# CAN_Module.net
KiCad netlist of a schematic drawn in EAGLE
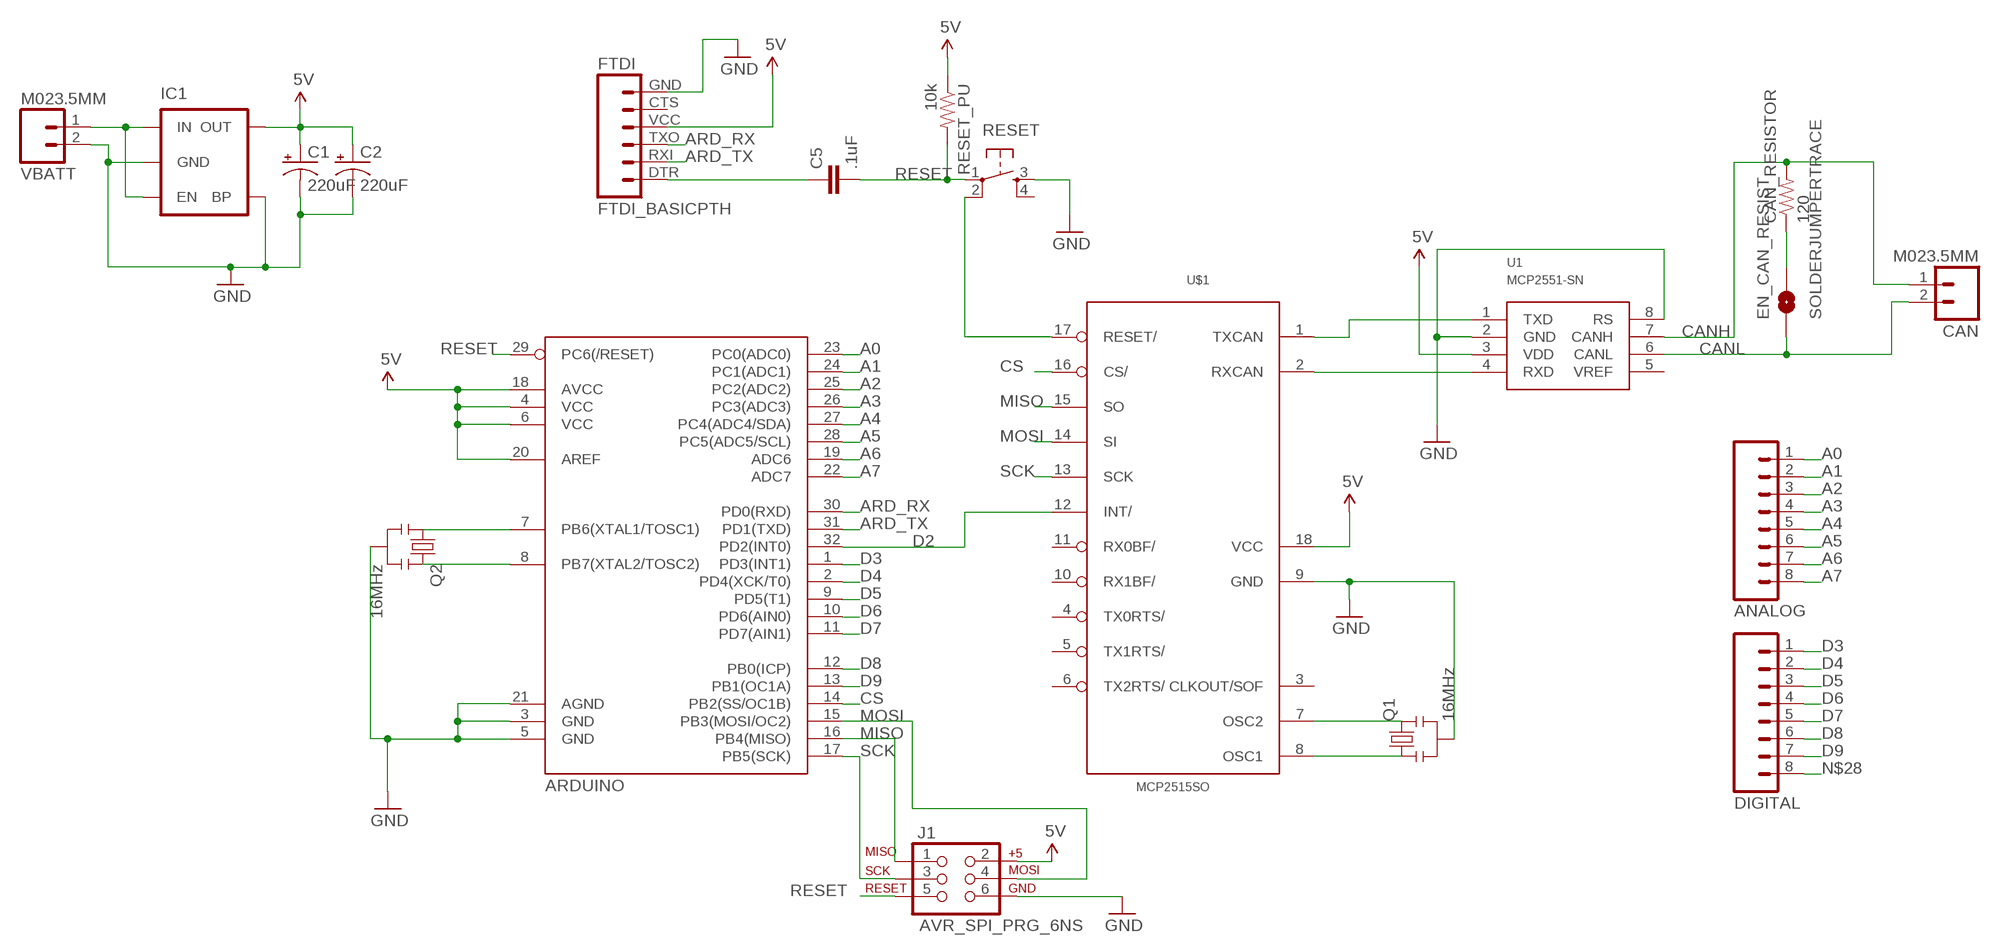
[diagram p0: schematic, sheet 1]

(export (version "E")
  (design (tool "Eeschema 10.0.6"))
  (components
    (comp (ref "ANALOG")
      (value "M08LOCK")
      (footprint "eagle-import:1X08_LOCK")
      (libsource (lib "eagle-import") (part "M08LOCK"))
    )
    (comp (ref "ARDUINO")
      (value "ATMEGA328_SMT")
      (footprint "eagle-import:TQFP32-08")
      (libsource (lib "eagle-import") (part "ATMEGA328_SMT"))
    )
    (comp (ref "C1")
      (value "220uF")
      (footprint "eagle-import:EIA3216-KIT")
      (libsource (lib "eagle-import") (part "CAP_POL1206-KIT"))
    )
    (comp (ref "C2")
      (value "220uF")
      (footprint "eagle-import:EIA3216-KIT")
      (libsource (lib "eagle-import") (part "CAP_POL1206-KIT"))
    )
    (comp (ref "C5")
      (value ".1uF")
      (footprint "eagle-import:0805")
      (libsource (lib "eagle-import") (part "CAP0805"))
    )
    (comp (ref "CAN")
      (value "M023.5MM")
      (footprint "eagle-import:SCREWTERMINAL-3.5MM-2")
      (libsource (lib "eagle-import") (part "M023.5MM"))
    )
    (comp (ref "CAN_RESISTOR")
      (value "120")
      (footprint "eagle-import:0805")
      (libsource (lib "eagle-import") (part "RESISTOR0805-RES"))
    )
    (comp (ref "DIGITAL")
      (value "M08LOCK")
      (footprint "eagle-import:1X08_LOCK")
      (libsource (lib "eagle-import") (part "M08LOCK"))
    )
    (comp (ref "EN_CAN_RESIST")
      (value "SOLDERJUMPERTRACE")
      (footprint "eagle-import:SJ_2S-TRACE")
      (libsource (lib "eagle-import") (part "SOLDERJUMPERTRACE"))
    )
    (comp (ref "FTDI")
      (value "FTDI_BASICPTH")
      (footprint "eagle-import:FTDI_BASIC")
      (libsource (lib "eagle-import") (part "FTDI_BASICPTH"))
    )
    (comp (ref "IC1")
      (value "MIC52055V")
      (footprint "eagle-import:SOT23-5")
      (libsource (lib "eagle-import") (part "MIC52055V"))
    )
    (comp (ref "J1")
      (value "AVR_SPI_PRG_6NS")
      (footprint "eagle-import:2X3-NS")
      (libsource (lib "eagle-import") (part "AVR_SPI_PRG_6NS"))
    )
    (comp (ref "Q1")
      (value "16MHz")
      (footprint "eagle-import:RESONATOR-SMD")
      (libsource (lib "eagle-import") (part "RESONATOR16MHZ"))
    )
    (comp (ref "Q2")
      (value "16MHz")
      (footprint "eagle-import:RESONATOR-SMD")
      (libsource (lib "eagle-import") (part "RESONATOR16MHZ"))
    )
    (comp (ref "RESET")
      (value "TAC_SWITCHSMD")
      (footprint "eagle-import:TACTILE_SWITCH_SMD")
      (libsource (lib "eagle-import") (part "TAC_SWITCHSMD"))
    )
    (comp (ref "RESET_PU")
      (value "10k")
      (footprint "eagle-import:0805")
      (libsource (lib "eagle-import") (part "RESISTOR0805-RES"))
    )
    (comp (ref "U$1")
      (value "MCP2515SO")
      (footprint "eagle-import:SO18L")
      (libsource (lib "eagle-import") (part "MCP2515SO"))
    )
    (comp (ref "U1")
      (value "MCP2551-SN")
      (footprint "eagle-import:SO-08")
      (libsource (lib "eagle-import") (part "MCP2551-SN"))
    )
    (comp (ref "VBATT")
      (value "M023.5MM")
      (footprint "eagle-import:SCREWTERMINAL-3.5MM-2")
      (libsource (lib "eagle-import") (part "M023.5MM"))
    )
  )
  (nets
    (net (code "1") (name "/A0") (class "Default")
      (node (ref "ANALOG") (pin "1") (pinfunction "1_1") (pintype "passive"))
      (node (ref "ARDUINO") (pin "23") (pinfunction "PC0(ADC0)_23") (pintype "bidirectional"))
    )
    (net (code "2") (name "/A1") (class "Default")
      (node (ref "ANALOG") (pin "2") (pinfunction "2_2") (pintype "passive"))
      (node (ref "ARDUINO") (pin "24") (pinfunction "PC1(ADC1)_24") (pintype "bidirectional"))
    )
    (net (code "3") (name "/A2") (class "Default")
      (node (ref "ANALOG") (pin "3") (pinfunction "3_3") (pintype "passive"))
      (node (ref "ARDUINO") (pin "25") (pinfunction "PC2(ADC2)_25") (pintype "bidirectional"))
    )
    (net (code "4") (name "/A3") (class "Default")
      (node (ref "ANALOG") (pin "4") (pinfunction "4_4") (pintype "passive"))
      (node (ref "ARDUINO") (pin "26") (pinfunction "PC3(ADC3)_26") (pintype "bidirectional"))
    )
    (net (code "5") (name "/A4") (class "Default")
      (node (ref "ANALOG") (pin "5") (pinfunction "5_5") (pintype "passive"))
      (node (ref "ARDUINO") (pin "27") (pinfunction "PC4(ADC4/SDA)_27") (pintype "bidirectional"))
    )
    (net (code "6") (name "/A5") (class "Default")
      (node (ref "ANALOG") (pin "6") (pinfunction "6_6") (pintype "passive"))
      (node (ref "ARDUINO") (pin "28") (pinfunction "PC5(ADC5/SCL)_28") (pintype "bidirectional"))
    )
    (net (code "7") (name "/A6") (class "Default")
      (node (ref "ANALOG") (pin "7") (pinfunction "7_7") (pintype "passive"))
      (node (ref "ARDUINO") (pin "19") (pinfunction "ADC6_19") (pintype "bidirectional"))
    )
    (net (code "8") (name "/A7") (class "Default")
      (node (ref "ANALOG") (pin "8") (pinfunction "8_8") (pintype "passive"))
      (node (ref "ARDUINO") (pin "22") (pinfunction "ADC7_22") (pintype "bidirectional"))
    )
    (net (code "9") (name "/ARD_RX") (class "Default")
      (node (ref "ARDUINO") (pin "30") (pinfunction "PD0(RXD)_30") (pintype "bidirectional"))
      (node (ref "FTDI") (pin "TXO") (pinfunction "3_TXO") (pintype "passive"))
    )
    (net (code "10") (name "/ARD_TX") (class "Default")
      (node (ref "ARDUINO") (pin "31") (pinfunction "PD1(TXD)_31") (pintype "bidirectional"))
      (node (ref "FTDI") (pin "RXI") (pinfunction "2_RXI") (pintype "passive"))
    )
    (net (code "11") (name "/CANH") (class "Default")
      (node (ref "CAN") (pin "1") (pinfunction "1_1") (pintype "passive"))
      (node (ref "CAN_RESISTOR") (pin "2") (pinfunction "2_2") (pintype "passive"))
      (node (ref "U1") (pin "7") (pinfunction "CANH_7") (pintype "bidirectional"))
    )
    (net (code "12") (name "/CANL") (class "Default")
      (node (ref "CAN") (pin "2") (pinfunction "2_2") (pintype "passive"))
      (node (ref "EN_CAN_RESIST") (pin "1") (pinfunction "1_1") (pintype "passive"))
      (node (ref "U1") (pin "6") (pinfunction "CANL_6") (pintype "bidirectional"))
    )
    (net (code "13") (name "/CS") (class "Default")
      (node (ref "ARDUINO") (pin "14") (pinfunction "PB2(SS/OC1B)_14") (pintype "bidirectional"))
      (node (ref "U$1") (pin "16") (pinfunction "CS/_16") (pintype "input"))
    )
    (net (code "14") (name "/D2") (class "Default")
      (node (ref "ARDUINO") (pin "32") (pinfunction "PD2(INT0)_32") (pintype "bidirectional"))
      (node (ref "U$1") (pin "12") (pinfunction "INT/_12") (pintype "output"))
    )
    (net (code "15") (name "/D3") (class "Default")
      (node (ref "ARDUINO") (pin "1") (pinfunction "PD3(INT1)_1") (pintype "bidirectional"))
      (node (ref "DIGITAL") (pin "1") (pinfunction "1_1") (pintype "passive"))
    )
    (net (code "16") (name "/D4") (class "Default")
      (node (ref "ARDUINO") (pin "2") (pinfunction "PD4(XCK/T0)_2") (pintype "bidirectional"))
      (node (ref "DIGITAL") (pin "2") (pinfunction "2_2") (pintype "passive"))
    )
    (net (code "17") (name "/D5") (class "Default")
      (node (ref "ARDUINO") (pin "9") (pinfunction "PD5(T1)_9") (pintype "bidirectional"))
      (node (ref "DIGITAL") (pin "3") (pinfunction "3_3") (pintype "passive"))
    )
    (net (code "18") (name "/D6") (class "Default")
      (node (ref "ARDUINO") (pin "10") (pinfunction "PD6(AIN0)_10") (pintype "bidirectional"))
      (node (ref "DIGITAL") (pin "4") (pinfunction "4_4") (pintype "passive"))
    )
    (net (code "19") (name "/D7") (class "Default")
      (node (ref "ARDUINO") (pin "11") (pinfunction "PD7(AIN1)_11") (pintype "bidirectional"))
      (node (ref "DIGITAL") (pin "5") (pinfunction "5_5") (pintype "passive"))
    )
    (net (code "20") (name "/D8") (class "Default")
      (node (ref "ARDUINO") (pin "12") (pinfunction "PB0(ICP)_12") (pintype "bidirectional"))
      (node (ref "DIGITAL") (pin "6") (pinfunction "6_6") (pintype "passive"))
    )
    (net (code "21") (name "/D9") (class "Default")
      (node (ref "ARDUINO") (pin "13") (pinfunction "PB1(OC1A)_13") (pintype "bidirectional"))
      (node (ref "DIGITAL") (pin "7") (pinfunction "7_7") (pintype "passive"))
    )
    (net (code "22") (name "/MISO") (class "Default")
      (node (ref "ARDUINO") (pin "16") (pinfunction "PB4(MISO)_16") (pintype "bidirectional"))
      (node (ref "J1") (pin "1") (pinfunction "1_1") (pintype "passive"))
      (node (ref "U$1") (pin "15") (pinfunction "SO_15") (pintype "output"))
    )
    (net (code "23") (name "/MOSI") (class "Default")
      (node (ref "ARDUINO") (pin "15") (pinfunction "PB3(MOSI/OC2)_15") (pintype "bidirectional"))
      (node (ref "J1") (pin "4") (pinfunction "4_4") (pintype "passive"))
      (node (ref "U$1") (pin "14") (pinfunction "SI_14") (pintype "input"))
    )
    (net (code "24") (name "/N$28") (class "Default")
      (node (ref "DIGITAL") (pin "8") (pinfunction "8_8") (pintype "passive"))
    )
    (net (code "25") (name "/RESET") (class "Default")
      (node (ref "ARDUINO") (pin "29") (pinfunction "PC6(/RESET)_29") (pintype "bidirectional"))
      (node (ref "C5") (pin "2") (pinfunction "2_2") (pintype "passive"))
      (node (ref "J1") (pin "5") (pinfunction "5_5") (pintype "passive"))
      (node (ref "RESET") (pin "1") (pinfunction "1_1") (pintype "passive"))
      (node (ref "RESET_PU") (pin "2") (pinfunction "2_2") (pintype "passive"))
    )
    (net (code "26") (name "/SCK") (class "Default")
      (node (ref "ARDUINO") (pin "17") (pinfunction "PB5(SCK)_17") (pintype "bidirectional"))
      (node (ref "J1") (pin "3") (pinfunction "3_3") (pintype "passive"))
      (node (ref "U$1") (pin "13") (pinfunction "SCK_13") (pintype "input"))
    )
    (net (code "27") (name "5V") (class "Default")
      (node (ref "ARDUINO") (pin "18") (pinfunction "AVCC_18") (pintype "bidirectional"))
      (node (ref "ARDUINO") (pin "20") (pinfunction "AREF_20") (pintype "bidirectional"))
      (node (ref "ARDUINO") (pin "4") (pinfunction "VCC_4") (pintype "bidirectional"))
      (node (ref "ARDUINO") (pin "6") (pinfunction "VCC_6") (pintype "bidirectional"))
      (node (ref "C1") (pin "A") (pinfunction "+_A") (pintype "passive"))
      (node (ref "C2") (pin "A") (pinfunction "+_A") (pintype "passive"))
      (node (ref "FTDI") (pin "VCC") (pinfunction "4_VCC") (pintype "passive"))
      (node (ref "IC1") (pin "5") (pinfunction "OUT_5") (pintype "passive"))
      (node (ref "J1") (pin "2") (pinfunction "2_2") (pintype "passive"))
      (node (ref "RESET_PU") (pin "1") (pinfunction "1_1") (pintype "passive"))
      (node (ref "U$1") (pin "18") (pinfunction "VCC_18") (pintype "power_in"))
      (node (ref "U1") (pin "3") (pinfunction "VDD_3") (pintype "power_in"))
    )
    (net (code "28") (name "GND") (class "Default")
      (node (ref "ARDUINO") (pin "21") (pinfunction "AGND_21") (pintype "bidirectional"))
      (node (ref "ARDUINO") (pin "3") (pinfunction "GND_3") (pintype "bidirectional"))
      (node (ref "ARDUINO") (pin "5") (pinfunction "GND_5") (pintype "bidirectional"))
      (node (ref "C1") (pin "C") (pinfunction "-_C") (pintype "passive"))
      (node (ref "C2") (pin "C") (pinfunction "-_C") (pintype "passive"))
      (node (ref "FTDI") (pin "GND") (pinfunction "6_GND") (pintype "passive"))
      (node (ref "IC1") (pin "2") (pinfunction "GND_2") (pintype "input"))
      (node (ref "IC1") (pin "4") (pinfunction "BP_4") (pintype "input"))
      (node (ref "J1") (pin "6") (pinfunction "6_6") (pintype "passive"))
      (node (ref "Q1") (pin "2") (pinfunction "2_2") (pintype "passive"))
      (node (ref "Q2") (pin "2") (pinfunction "2_2") (pintype "passive"))
      (node (ref "RESET") (pin "3") (pinfunction "3_3") (pintype "passive"))
      (node (ref "U$1") (pin "9") (pinfunction "GND_9") (pintype "power_in"))
      (node (ref "U1") (pin "2") (pinfunction "GND_2") (pintype "power_in"))
      (node (ref "U1") (pin "8") (pinfunction "RS_8") (pintype "output"))
      (node (ref "VBATT") (pin "2") (pinfunction "2_2") (pintype "passive"))
    )
    (net (code "29") (name "Net-(ARDUINO-PB6(XTAL1{slash}TOSC1))") (class "Default")
      (node (ref "ARDUINO") (pin "7") (pinfunction "PB6(XTAL1/TOSC1)_7") (pintype "bidirectional"))
      (node (ref "Q2") (pin "1") (pinfunction "1_1") (pintype "passive"))
    )
    (net (code "30") (name "Net-(ARDUINO-PB7(XTAL2{slash}TOSC2))") (class "Default")
      (node (ref "ARDUINO") (pin "8") (pinfunction "PB7(XTAL2/TOSC2)_8") (pintype "bidirectional"))
      (node (ref "Q2") (pin "3") (pinfunction "3_3") (pintype "passive"))
    )
    (net (code "31") (name "Net-(CAN_RESISTOR-Pad1)") (class "Default")
      (node (ref "CAN_RESISTOR") (pin "1") (pinfunction "1_1") (pintype "passive"))
      (node (ref "EN_CAN_RESIST") (pin "2") (pinfunction "2_2") (pintype "passive"))
    )
    (net (code "32") (name "Net-(FTDI-1)") (class "Default")
      (node (ref "C5") (pin "1") (pinfunction "1_1") (pintype "passive"))
      (node (ref "FTDI") (pin "DTR") (pinfunction "1_DTR") (pintype "passive"))
    )
    (net (code "33") (name "Net-(IC1-EN)") (class "Default")
      (node (ref "IC1") (pin "1") (pinfunction "IN_1") (pintype "input"))
      (node (ref "IC1") (pin "3") (pinfunction "EN_3") (pintype "input"))
      (node (ref "VBATT") (pin "1") (pinfunction "1_1") (pintype "passive"))
    )
    (net (code "34") (name "Net-(U$1-OSC1)") (class "Default")
      (node (ref "Q1") (pin "1") (pinfunction "1_1") (pintype "passive"))
      (node (ref "U$1") (pin "8") (pinfunction "OSC1_8") (pintype "bidirectional"))
    )
    (net (code "35") (name "Net-(U$1-OSC2)") (class "Default")
      (node (ref "Q1") (pin "3") (pinfunction "3_3") (pintype "passive"))
      (node (ref "U$1") (pin "7") (pinfunction "OSC2_7") (pintype "bidirectional"))
    )
    (net (code "36") (name "Net-(U$1-RESET{slash})") (class "Default")
      (node (ref "RESET") (pin "2") (pinfunction "2_2") (pintype "passive"))
      (node (ref "U$1") (pin "17") (pinfunction "RESET/_17") (pintype "input"))
    )
    (net (code "37") (name "Net-(U$1-RXCAN)") (class "Default")
      (node (ref "U$1") (pin "2") (pinfunction "RXCAN_2") (pintype "input"))
      (node (ref "U1") (pin "4") (pinfunction "RXD_4") (pintype "input"))
    )
    (net (code "38") (name "Net-(U$1-TXCAN)") (class "Default")
      (node (ref "U$1") (pin "1") (pinfunction "TXCAN_1") (pintype "output"))
      (node (ref "U1") (pin "1") (pinfunction "TXD_1") (pintype "output"))
    )
    (net (code "39") (name "unconnected-(FTDI-5-PadCTS)") (class "Default")
      (node (ref "FTDI") (pin "CTS") (pinfunction "5_CTS") (pintype "passive"))
    )
    (net (code "40") (name "unconnected-(RESET-Pad4)") (class "Default")
      (node (ref "RESET") (pin "4") (pinfunction "4_4") (pintype "passive"))
    )
    (net (code "41") (name "unconnected-(U$1-CLKOUT{slash}SOF-Pad3)") (class "Default")
      (node (ref "U$1") (pin "3") (pinfunction "CLKOUT/SOF_3") (pintype "bidirectional"))
    )
    (net (code "42") (name "unconnected-(U$1-RX0BF{slash}-Pad11)") (class "Default")
      (node (ref "U$1") (pin "11") (pinfunction "RX0BF/_11") (pintype "bidirectional"))
    )
    (net (code "43") (name "unconnected-(U$1-RX1BF{slash}-Pad10)") (class "Default")
      (node (ref "U$1") (pin "10") (pinfunction "RX1BF/_10") (pintype "bidirectional"))
    )
    (net (code "44") (name "unconnected-(U$1-TX0RTS{slash}-Pad4)") (class "Default")
      (node (ref "U$1") (pin "4") (pinfunction "TX0RTS/_4") (pintype "bidirectional"))
    )
    (net (code "45") (name "unconnected-(U$1-TX1RTS{slash}-Pad5)") (class "Default")
      (node (ref "U$1") (pin "5") (pinfunction "TX1RTS/_5") (pintype "bidirectional"))
    )
    (net (code "46") (name "unconnected-(U$1-TX2RTS{slash}-Pad6)") (class "Default")
      (node (ref "U$1") (pin "6") (pinfunction "TX2RTS/_6") (pintype "bidirectional"))
    )
    (net (code "47") (name "unconnected-(U1-VREF-Pad5)") (class "Default")
      (node (ref "U1") (pin "5") (pinfunction "VREF_5") (pintype "output"))
    )
  )
)
